# PCB-4SLIDER20.net
KiCad netlist of a schematic drawn in EAGLE
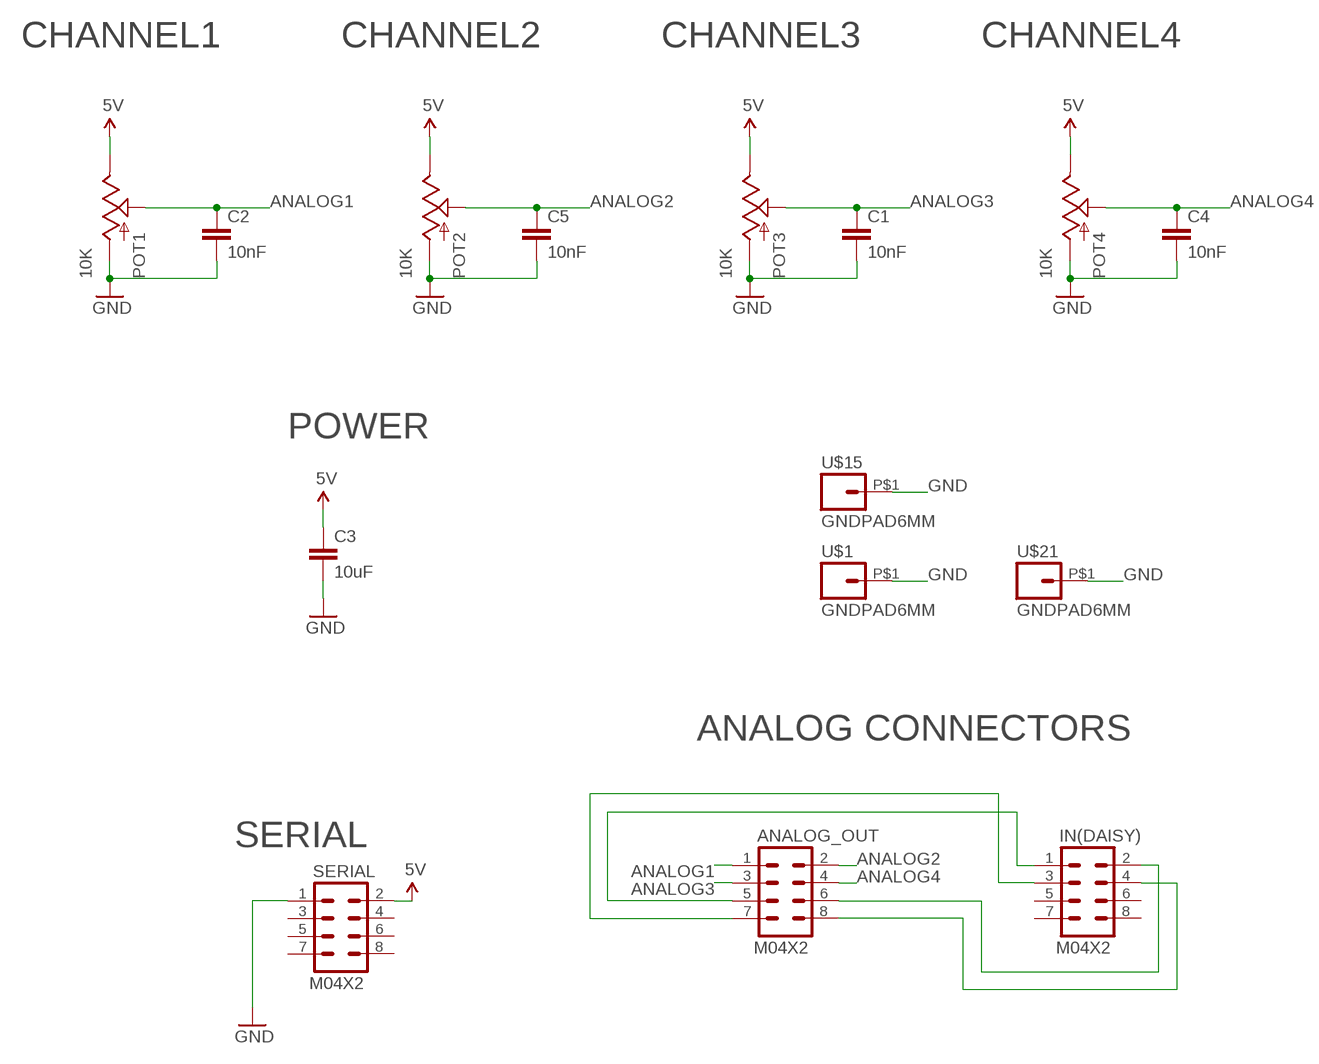
[diagram p0: schematic, sheet 1]

(export (version "E")
  (design (tool "Eeschema 10.0.6"))
  (components
    (comp (ref "ANALOG_OUT")
      (value "M04X2")
      (footprint "eagle-import:2X4")
      (libsource (lib "eagle-import") (part "M04X2"))
    )
    (comp (ref "C1")
      (value "10nF")
      (footprint "eagle-import:0603-CAP")
      (libsource (lib "eagle-import") (part "CAP0603-CAP"))
    )
    (comp (ref "C2")
      (value "10nF")
      (footprint "eagle-import:0603-CAP")
      (libsource (lib "eagle-import") (part "CAP0603-CAP"))
    )
    (comp (ref "C3")
      (value "10uF")
      (footprint "eagle-import:0805")
      (libsource (lib "eagle-import") (part "CAP0805"))
    )
    (comp (ref "C4")
      (value "10nF")
      (footprint "eagle-import:0603-CAP")
      (libsource (lib "eagle-import") (part "CAP0603-CAP"))
    )
    (comp (ref "C5")
      (value "10nF")
      (footprint "eagle-import:0603-CAP")
      (libsource (lib "eagle-import") (part "CAP0603-CAP"))
    )
    (comp (ref "IN(DAISY)")
      (value "M04X2")
      (footprint "eagle-import:2X4")
      (libsource (lib "eagle-import") (part "M04X2"))
    )
    (comp (ref "POT1")
      (value "10K")
      (footprint "eagle-import:SLIDER20")
      (libsource (lib "eagle-import") (part "SLIDER20"))
    )
    (comp (ref "POT2")
      (value "10K")
      (footprint "eagle-import:SLIDER20")
      (libsource (lib "eagle-import") (part "SLIDER20"))
    )
    (comp (ref "POT3")
      (value "10K")
      (footprint "eagle-import:SLIDER20")
      (libsource (lib "eagle-import") (part "SLIDER20"))
    )
    (comp (ref "POT4")
      (value "10K")
      (footprint "eagle-import:SLIDER20")
      (libsource (lib "eagle-import") (part "SLIDER20"))
    )
    (comp (ref "SERIAL")
      (value "M04X2")
      (footprint "eagle-import:2X4")
      (libsource (lib "eagle-import") (part "M04X2"))
    )
    (comp (ref "U$1")
      (value "GNDPAD6MM")
      (footprint "eagle-import:3.2MMPAD6MM")
      (libsource (lib "eagle-import") (part "GNDPAD6MM"))
    )
    (comp (ref "U$15")
      (value "GNDPAD6MM")
      (footprint "eagle-import:3.2MMPAD6MM")
      (libsource (lib "eagle-import") (part "GNDPAD6MM"))
    )
    (comp (ref "U$21")
      (value "GNDPAD6MM")
      (footprint "eagle-import:3.2MMPAD6MM")
      (libsource (lib "eagle-import") (part "GNDPAD6MM"))
    )
  )
  (nets
    (net (code "1") (name "5V") (class "Default")
      (node (ref "C3") (pin "1") (pinfunction "1_1") (pintype "passive"))
      (node (ref "POT1") (pin "1") (pinfunction "E_1") (pintype "passive"))
      (node (ref "POT2") (pin "1") (pinfunction "E_1") (pintype "passive"))
      (node (ref "POT3") (pin "1") (pinfunction "E_1") (pintype "passive"))
      (node (ref "POT4") (pin "1") (pinfunction "E_1") (pintype "passive"))
      (node (ref "SERIAL") (pin "2") (pinfunction "2_2") (pintype "passive"))
    )
    (net (code "2") (name "ANALOG1") (class "Default")
      (node (ref "ANALOG_OUT") (pin "1") (pinfunction "1_1") (pintype "passive"))
      (node (ref "C2") (pin "1") (pinfunction "1_1") (pintype "passive"))
      (node (ref "POT1") (pin "2A") (pinfunction "S_2A") (pintype "passive"))
    )
    (net (code "3") (name "ANALOG2") (class "Default")
      (node (ref "ANALOG_OUT") (pin "2") (pinfunction "2_2") (pintype "passive"))
      (node (ref "C5") (pin "1") (pinfunction "1_1") (pintype "passive"))
      (node (ref "POT2") (pin "2A") (pinfunction "S_2A") (pintype "passive"))
    )
    (net (code "4") (name "ANALOG3") (class "Default")
      (node (ref "ANALOG_OUT") (pin "3") (pinfunction "3_3") (pintype "passive"))
      (node (ref "C1") (pin "1") (pinfunction "1_1") (pintype "passive"))
      (node (ref "POT3") (pin "2A") (pinfunction "S_2A") (pintype "passive"))
    )
    (net (code "5") (name "ANALOG4") (class "Default")
      (node (ref "ANALOG_OUT") (pin "4") (pinfunction "4_4") (pintype "passive"))
      (node (ref "C4") (pin "1") (pinfunction "1_1") (pintype "passive"))
      (node (ref "POT4") (pin "2A") (pinfunction "S_2A") (pintype "passive"))
    )
    (net (code "6") (name "GND") (class "Default")
      (node (ref "C1") (pin "2") (pinfunction "2_2") (pintype "passive"))
      (node (ref "C2") (pin "2") (pinfunction "2_2") (pintype "passive"))
      (node (ref "C3") (pin "2") (pinfunction "2_2") (pintype "passive"))
      (node (ref "C4") (pin "2") (pinfunction "2_2") (pintype "passive"))
      (node (ref "C5") (pin "2") (pinfunction "2_2") (pintype "passive"))
      (node (ref "POT1") (pin "3") (pinfunction "A_3") (pintype "passive"))
      (node (ref "POT2") (pin "3") (pinfunction "A_3") (pintype "passive"))
      (node (ref "POT3") (pin "3") (pinfunction "A_3") (pintype "passive"))
      (node (ref "POT4") (pin "3") (pinfunction "A_3") (pintype "passive"))
      (node (ref "SERIAL") (pin "1") (pinfunction "1_1") (pintype "passive"))
      (node (ref "U$1") (pin "P$1") (pinfunction "1_P$1") (pintype "passive"))
      (node (ref "U$15") (pin "P$1") (pinfunction "1_P$1") (pintype "passive"))
      (node (ref "U$21") (pin "P$1") (pinfunction "1_P$1") (pintype "passive"))
    )
    (net (code "7") (name "Net-(ANALOG_OUT-Pad5)") (class "Default")
      (node (ref "ANALOG_OUT") (pin "5") (pinfunction "5_5") (pintype "passive"))
      (node (ref "IN(DAISY)") (pin "1") (pinfunction "1_1") (pintype "passive"))
    )
    (net (code "8") (name "Net-(ANALOG_OUT-Pad6)") (class "Default")
      (node (ref "ANALOG_OUT") (pin "6") (pinfunction "6_6") (pintype "passive"))
      (node (ref "IN(DAISY)") (pin "2") (pinfunction "2_2") (pintype "passive"))
    )
    (net (code "9") (name "Net-(ANALOG_OUT-Pad7)") (class "Default")
      (node (ref "ANALOG_OUT") (pin "7") (pinfunction "7_7") (pintype "passive"))
      (node (ref "IN(DAISY)") (pin "3") (pinfunction "3_3") (pintype "passive"))
    )
    (net (code "10") (name "Net-(ANALOG_OUT-Pad8)") (class "Default")
      (node (ref "ANALOG_OUT") (pin "8") (pinfunction "8_8") (pintype "passive"))
      (node (ref "IN(DAISY)") (pin "4") (pinfunction "4_4") (pintype "passive"))
    )
    (net (code "11") (name "unconnected-(IN(DAISY)-Pad5)") (class "Default")
      (node (ref "IN(DAISY)") (pin "5") (pinfunction "5_5") (pintype "passive"))
    )
    (net (code "12") (name "unconnected-(IN(DAISY)-Pad6)") (class "Default")
      (node (ref "IN(DAISY)") (pin "6") (pinfunction "6_6") (pintype "passive"))
    )
    (net (code "13") (name "unconnected-(IN(DAISY)-Pad7)") (class "Default")
      (node (ref "IN(DAISY)") (pin "7") (pinfunction "7_7") (pintype "passive"))
    )
    (net (code "14") (name "unconnected-(IN(DAISY)-Pad8)") (class "Default")
      (node (ref "IN(DAISY)") (pin "8") (pinfunction "8_8") (pintype "passive"))
    )
    (net (code "15") (name "unconnected-(SERIAL-Pad3)") (class "Default")
      (node (ref "SERIAL") (pin "3") (pinfunction "3_3") (pintype "passive"))
    )
    (net (code "16") (name "unconnected-(SERIAL-Pad4)") (class "Default")
      (node (ref "SERIAL") (pin "4") (pinfunction "4_4") (pintype "passive"))
    )
    (net (code "17") (name "unconnected-(SERIAL-Pad5)") (class "Default")
      (node (ref "SERIAL") (pin "5") (pinfunction "5_5") (pintype "passive"))
    )
    (net (code "18") (name "unconnected-(SERIAL-Pad6)") (class "Default")
      (node (ref "SERIAL") (pin "6") (pinfunction "6_6") (pintype "passive"))
    )
    (net (code "19") (name "unconnected-(SERIAL-Pad7)") (class "Default")
      (node (ref "SERIAL") (pin "7") (pinfunction "7_7") (pintype "passive"))
    )
    (net (code "20") (name "unconnected-(SERIAL-Pad8)") (class "Default")
      (node (ref "SERIAL") (pin "8") (pinfunction "8_8") (pintype "passive"))
    )
  )
)
